# ProPatch_Main.net
KiCad netlist of a schematic drawn in Altium Designer
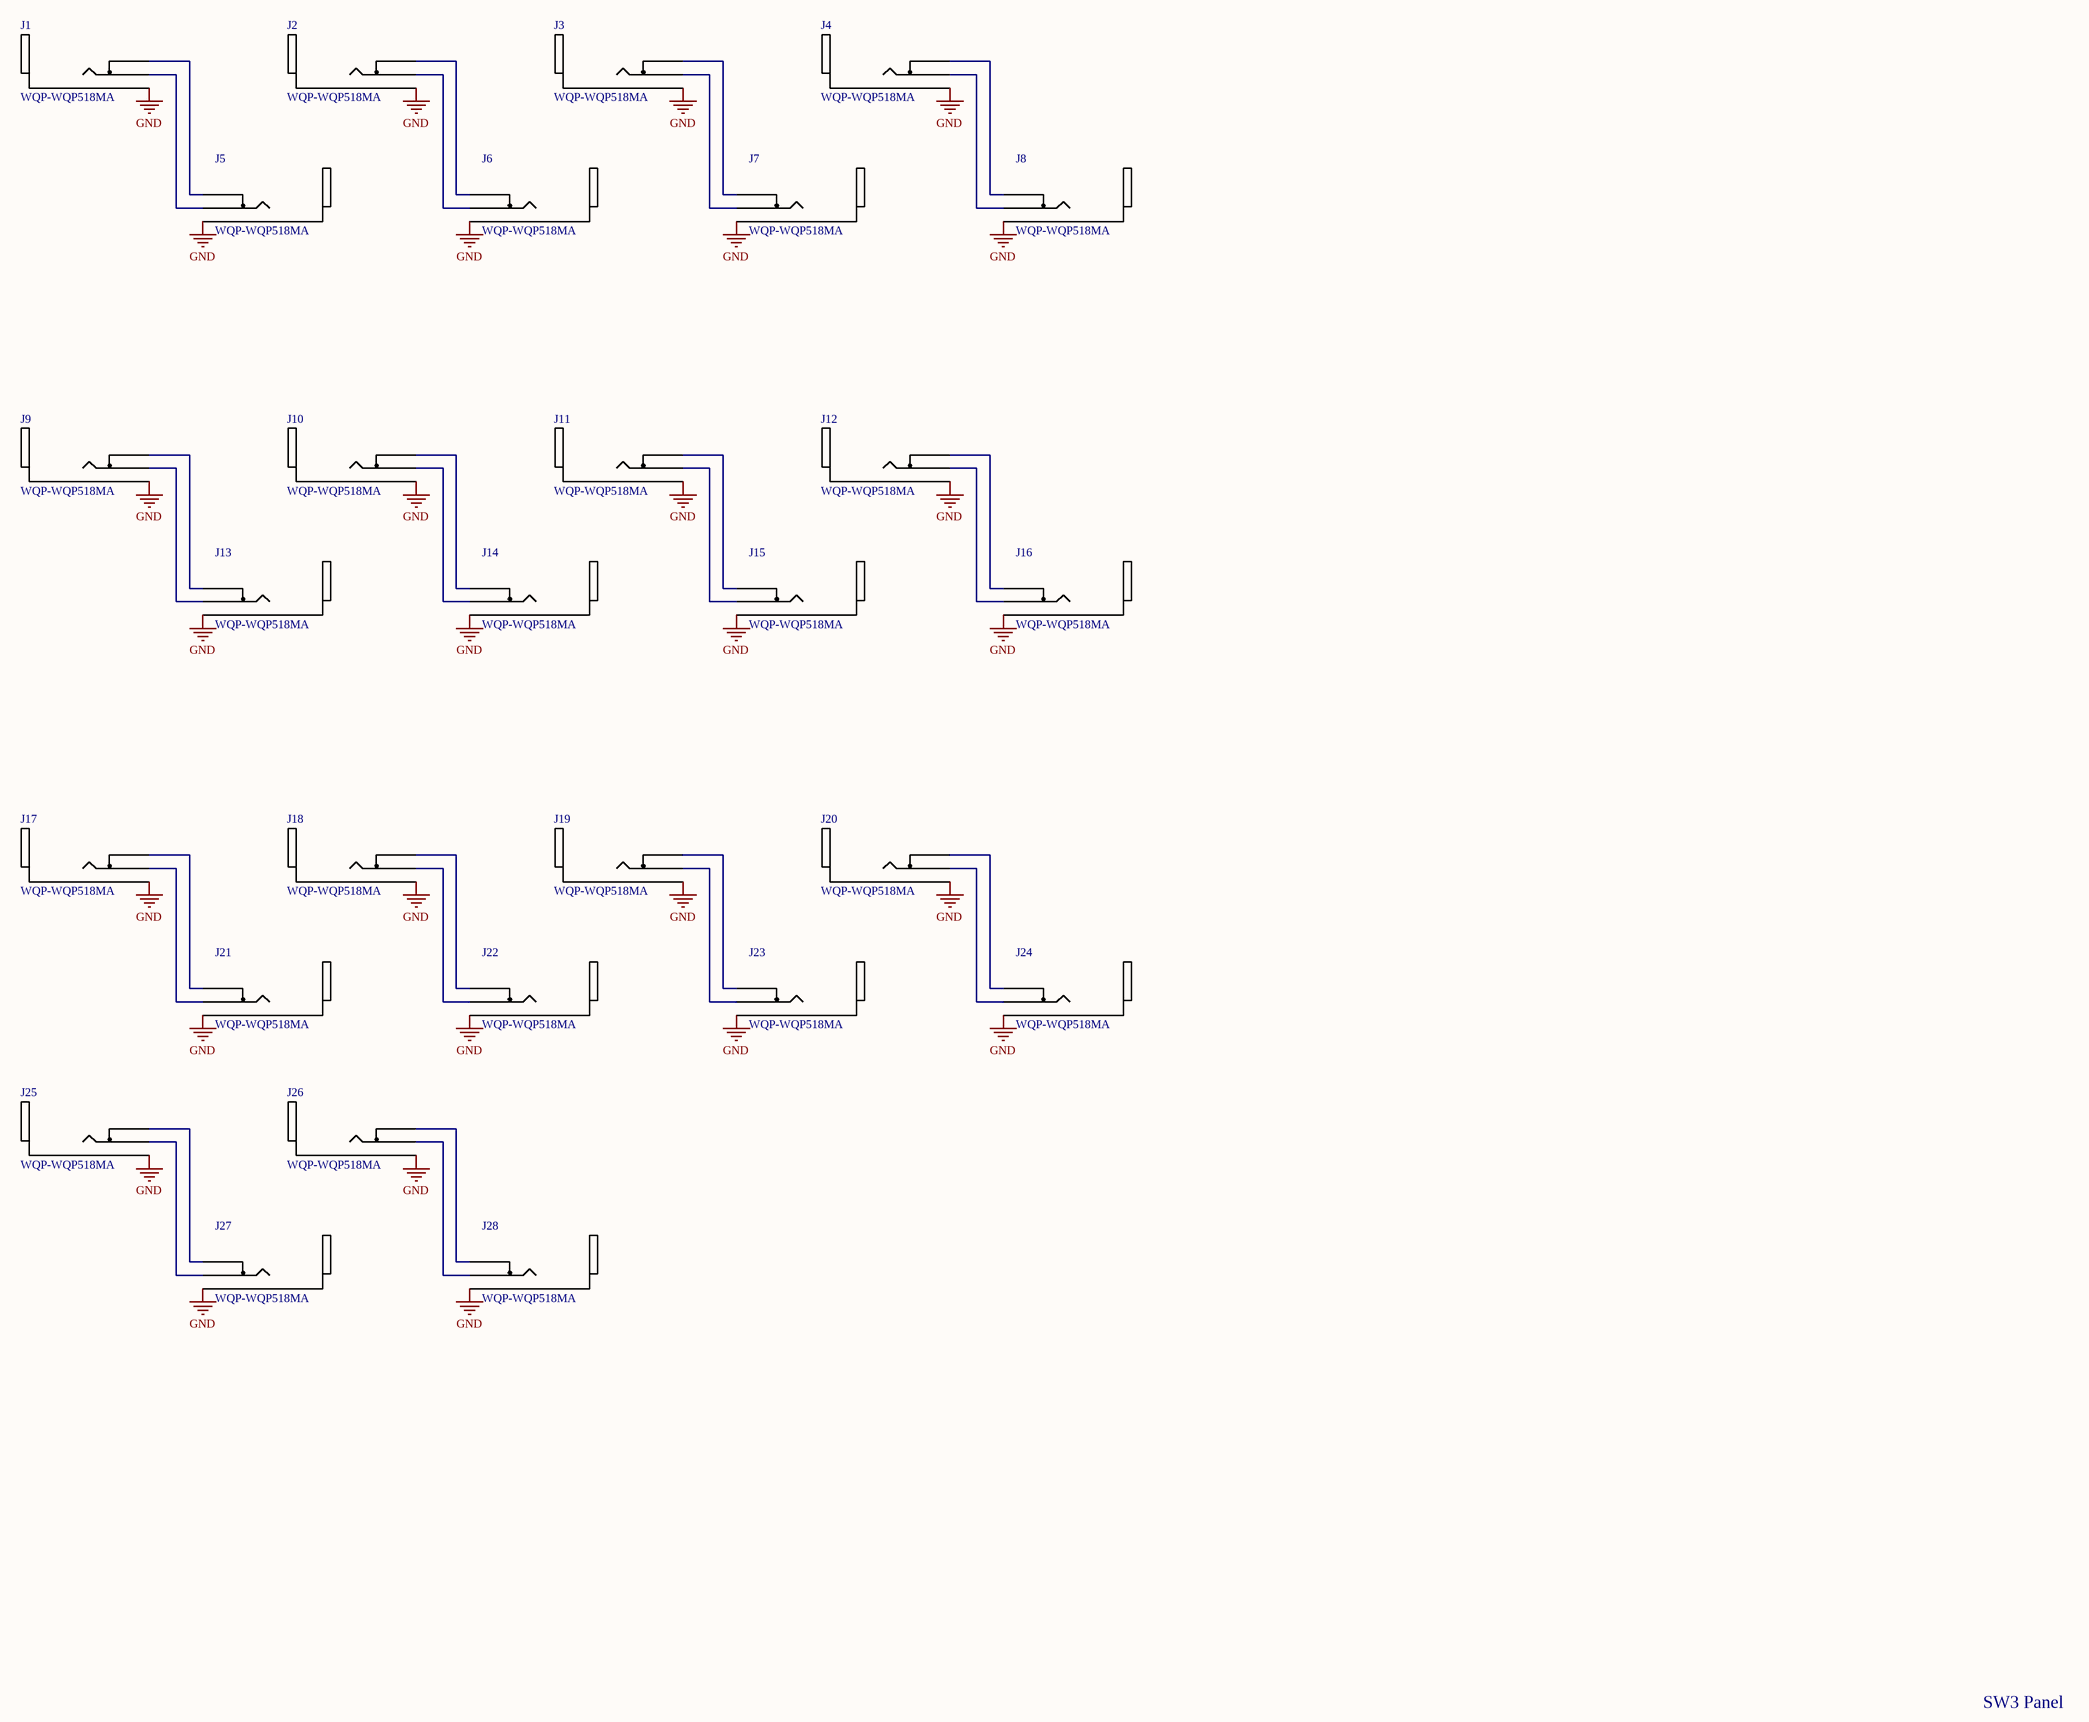
[diagram p0: ProPatch Main.SchDoc]

(export (version "E")
  (design (tool "Eeschema 10.0.6"))
  (components
    (comp (ref "J1")
      (value "WQP-WQP518MA")
      (footprint "PJ301M-12")
      (description "CONN 3.5mm VIRTICAL MONO w/ NORMAL")
      (fields (field (name "MANUFACTURER") "QingPu"))
      (libsource (lib "Connectors") (part "PJ301M-12"))
    )
    (comp (ref "J2")
      (value "WQP-WQP518MA")
      (footprint "PJ301M-12")
      (description "CONN 3.5mm VIRTICAL MONO w/ NORMAL")
      (fields (field (name "MANUFACTURER") "QingPu"))
      (libsource (lib "Connectors") (part "PJ301M-12"))
    )
    (comp (ref "J3")
      (value "WQP-WQP518MA")
      (footprint "PJ301M-12")
      (description "CONN 3.5mm VIRTICAL MONO w/ NORMAL")
      (fields (field (name "MANUFACTURER") "QingPu"))
      (libsource (lib "Connectors") (part "PJ301M-12"))
    )
    (comp (ref "J4")
      (value "WQP-WQP518MA")
      (footprint "PJ301M-12")
      (description "CONN 3.5mm VIRTICAL MONO w/ NORMAL")
      (fields (field (name "MANUFACTURER") "QingPu"))
      (libsource (lib "Connectors") (part "PJ301M-12"))
    )
    (comp (ref "J5")
      (value "WQP-WQP518MA")
      (footprint "PJ301M-12")
      (description "CONN 3.5mm VIRTICAL MONO w/ NORMAL")
      (fields (field (name "MANUFACTURER") "QingPu"))
      (libsource (lib "Connectors") (part "PJ301M-12"))
    )
    (comp (ref "J6")
      (value "WQP-WQP518MA")
      (footprint "PJ301M-12")
      (description "CONN 3.5mm VIRTICAL MONO w/ NORMAL")
      (fields (field (name "MANUFACTURER") "QingPu"))
      (libsource (lib "Connectors") (part "PJ301M-12"))
    )
    (comp (ref "J7")
      (value "WQP-WQP518MA")
      (footprint "PJ301M-12")
      (description "CONN 3.5mm VIRTICAL MONO w/ NORMAL")
      (fields (field (name "MANUFACTURER") "QingPu"))
      (libsource (lib "Connectors") (part "PJ301M-12"))
    )
    (comp (ref "J8")
      (value "WQP-WQP518MA")
      (footprint "PJ301M-12")
      (description "CONN 3.5mm VIRTICAL MONO w/ NORMAL")
      (fields (field (name "MANUFACTURER") "QingPu"))
      (libsource (lib "Connectors") (part "PJ301M-12"))
    )
    (comp (ref "J9")
      (value "WQP-WQP518MA")
      (footprint "PJ301M-12")
      (description "CONN 3.5mm VIRTICAL MONO w/ NORMAL")
      (fields (field (name "MANUFACTURER") "QingPu"))
      (libsource (lib "Connectors") (part "PJ301M-12"))
    )
    (comp (ref "J10")
      (value "WQP-WQP518MA")
      (footprint "PJ301M-12")
      (description "CONN 3.5mm VIRTICAL MONO w/ NORMAL")
      (fields (field (name "MANUFACTURER") "QingPu"))
      (libsource (lib "Connectors") (part "PJ301M-12"))
    )
    (comp (ref "J11")
      (value "WQP-WQP518MA")
      (footprint "PJ301M-12")
      (description "CONN 3.5mm VIRTICAL MONO w/ NORMAL")
      (fields (field (name "MANUFACTURER") "QingPu"))
      (libsource (lib "Connectors") (part "PJ301M-12"))
    )
    (comp (ref "J12")
      (value "WQP-WQP518MA")
      (footprint "PJ301M-12")
      (description "CONN 3.5mm VIRTICAL MONO w/ NORMAL")
      (fields (field (name "MANUFACTURER") "QingPu"))
      (libsource (lib "Connectors") (part "PJ301M-12"))
    )
    (comp (ref "J13")
      (value "WQP-WQP518MA")
      (footprint "PJ301M-12")
      (description "CONN 3.5mm VIRTICAL MONO w/ NORMAL")
      (fields (field (name "MANUFACTURER") "QingPu"))
      (libsource (lib "Connectors") (part "PJ301M-12"))
    )
    (comp (ref "J14")
      (value "WQP-WQP518MA")
      (footprint "PJ301M-12")
      (description "CONN 3.5mm VIRTICAL MONO w/ NORMAL")
      (fields (field (name "MANUFACTURER") "QingPu"))
      (libsource (lib "Connectors") (part "PJ301M-12"))
    )
    (comp (ref "J15")
      (value "WQP-WQP518MA")
      (footprint "PJ301M-12")
      (description "CONN 3.5mm VIRTICAL MONO w/ NORMAL")
      (fields (field (name "MANUFACTURER") "QingPu"))
      (libsource (lib "Connectors") (part "PJ301M-12"))
    )
    (comp (ref "J16")
      (value "WQP-WQP518MA")
      (footprint "PJ301M-12")
      (description "CONN 3.5mm VIRTICAL MONO w/ NORMAL")
      (fields (field (name "MANUFACTURER") "QingPu"))
      (libsource (lib "Connectors") (part "PJ301M-12"))
    )
    (comp (ref "J17")
      (value "WQP-WQP518MA")
      (footprint "PJ301M-12")
      (description "CONN 3.5mm VIRTICAL MONO w/ NORMAL")
      (fields (field (name "MANUFACTURER") "QingPu"))
      (libsource (lib "Connectors") (part "PJ301M-12"))
    )
    (comp (ref "J18")
      (value "WQP-WQP518MA")
      (footprint "PJ301M-12")
      (description "CONN 3.5mm VIRTICAL MONO w/ NORMAL")
      (fields (field (name "MANUFACTURER") "QingPu"))
      (libsource (lib "Connectors") (part "PJ301M-12"))
    )
    (comp (ref "J19")
      (value "WQP-WQP518MA")
      (footprint "PJ301M-12")
      (description "CONN 3.5mm VIRTICAL MONO w/ NORMAL")
      (fields (field (name "MANUFACTURER") "QingPu"))
      (libsource (lib "Connectors") (part "PJ301M-12"))
    )
    (comp (ref "J20")
      (value "WQP-WQP518MA")
      (footprint "PJ301M-12")
      (description "CONN 3.5mm VIRTICAL MONO w/ NORMAL")
      (fields (field (name "MANUFACTURER") "QingPu"))
      (libsource (lib "Connectors") (part "PJ301M-12"))
    )
    (comp (ref "J21")
      (value "WQP-WQP518MA")
      (footprint "PJ301M-12")
      (description "CONN 3.5mm VIRTICAL MONO w/ NORMAL")
      (fields (field (name "MANUFACTURER") "QingPu"))
      (libsource (lib "Connectors") (part "PJ301M-12"))
    )
    (comp (ref "J22")
      (value "WQP-WQP518MA")
      (footprint "PJ301M-12")
      (description "CONN 3.5mm VIRTICAL MONO w/ NORMAL")
      (fields (field (name "MANUFACTURER") "QingPu"))
      (libsource (lib "Connectors") (part "PJ301M-12"))
    )
    (comp (ref "J23")
      (value "WQP-WQP518MA")
      (footprint "PJ301M-12")
      (description "CONN 3.5mm VIRTICAL MONO w/ NORMAL")
      (fields (field (name "MANUFACTURER") "QingPu"))
      (libsource (lib "Connectors") (part "PJ301M-12"))
    )
    (comp (ref "J24")
      (value "WQP-WQP518MA")
      (footprint "PJ301M-12")
      (description "CONN 3.5mm VIRTICAL MONO w/ NORMAL")
      (fields (field (name "MANUFACTURER") "QingPu"))
      (libsource (lib "Connectors") (part "PJ301M-12"))
    )
    (comp (ref "J25")
      (value "WQP-WQP518MA")
      (footprint "PJ301M-12")
      (description "CONN 3.5mm VIRTICAL MONO w/ NORMAL")
      (fields (field (name "MANUFACTURER") "QingPu"))
      (libsource (lib "Connectors") (part "PJ301M-12"))
    )
    (comp (ref "J26")
      (value "WQP-WQP518MA")
      (footprint "PJ301M-12")
      (description "CONN 3.5mm VIRTICAL MONO w/ NORMAL")
      (fields (field (name "MANUFACTURER") "QingPu"))
      (libsource (lib "Connectors") (part "PJ301M-12"))
    )
    (comp (ref "J27")
      (value "WQP-WQP518MA")
      (footprint "PJ301M-12")
      (description "CONN 3.5mm VIRTICAL MONO w/ NORMAL")
      (fields (field (name "MANUFACTURER") "QingPu"))
      (libsource (lib "Connectors") (part "PJ301M-12"))
    )
    (comp (ref "J28")
      (value "WQP-WQP518MA")
      (footprint "PJ301M-12")
      (description "CONN 3.5mm VIRTICAL MONO w/ NORMAL")
      (fields (field (name "MANUFACTURER") "QingPu"))
      (libsource (lib "Connectors") (part "PJ301M-12"))
    )
  )
  (nets
    (net (code "1") (name "GND") (class "Default")
      (node (ref "J1") (pin "1") (pinfunction "1_1") (pintype "passive"))
      (node (ref "J10") (pin "1") (pinfunction "1_1") (pintype "passive"))
      (node (ref "J11") (pin "1") (pinfunction "1_1") (pintype "passive"))
      (node (ref "J12") (pin "1") (pinfunction "1_1") (pintype "passive"))
      (node (ref "J13") (pin "1") (pinfunction "1_1") (pintype "passive"))
      (node (ref "J14") (pin "1") (pinfunction "1_1") (pintype "passive"))
      (node (ref "J15") (pin "1") (pinfunction "1_1") (pintype "passive"))
      (node (ref "J16") (pin "1") (pinfunction "1_1") (pintype "passive"))
      (node (ref "J17") (pin "1") (pinfunction "1_1") (pintype "passive"))
      (node (ref "J18") (pin "1") (pinfunction "1_1") (pintype "passive"))
      (node (ref "J19") (pin "1") (pinfunction "1_1") (pintype "passive"))
      (node (ref "J2") (pin "1") (pinfunction "1_1") (pintype "passive"))
      (node (ref "J20") (pin "1") (pinfunction "1_1") (pintype "passive"))
      (node (ref "J21") (pin "1") (pinfunction "1_1") (pintype "passive"))
      (node (ref "J22") (pin "1") (pinfunction "1_1") (pintype "passive"))
      (node (ref "J23") (pin "1") (pinfunction "1_1") (pintype "passive"))
      (node (ref "J24") (pin "1") (pinfunction "1_1") (pintype "passive"))
      (node (ref "J25") (pin "1") (pinfunction "1_1") (pintype "passive"))
      (node (ref "J26") (pin "1") (pinfunction "1_1") (pintype "passive"))
      (node (ref "J27") (pin "1") (pinfunction "1_1") (pintype "passive"))
      (node (ref "J28") (pin "1") (pinfunction "1_1") (pintype "passive"))
      (node (ref "J3") (pin "1") (pinfunction "1_1") (pintype "passive"))
      (node (ref "J4") (pin "1") (pinfunction "1_1") (pintype "passive"))
      (node (ref "J5") (pin "1") (pinfunction "1_1") (pintype "passive"))
      (node (ref "J6") (pin "1") (pinfunction "1_1") (pintype "passive"))
      (node (ref "J7") (pin "1") (pinfunction "1_1") (pintype "passive"))
      (node (ref "J8") (pin "1") (pinfunction "1_1") (pintype "passive"))
      (node (ref "J9") (pin "1") (pinfunction "1_1") (pintype "passive"))
    )
    (net (code "2") (name "Net-(J1-Pad2)") (class "Default")
      (node (ref "J1") (pin "2") (pinfunction "2_2") (pintype "passive"))
      (node (ref "J5") (pin "2") (pinfunction "2_2") (pintype "passive"))
    )
    (net (code "3") (name "Net-(J1-Pad3)") (class "Default")
      (node (ref "J1") (pin "3") (pinfunction "3_3") (pintype "passive"))
      (node (ref "J5") (pin "3") (pinfunction "3_3") (pintype "passive"))
    )
    (net (code "4") (name "Net-(J2-Pad2)") (class "Default")
      (node (ref "J2") (pin "2") (pinfunction "2_2") (pintype "passive"))
      (node (ref "J6") (pin "2") (pinfunction "2_2") (pintype "passive"))
    )
    (net (code "5") (name "Net-(J2-Pad3)") (class "Default")
      (node (ref "J2") (pin "3") (pinfunction "3_3") (pintype "passive"))
      (node (ref "J6") (pin "3") (pinfunction "3_3") (pintype "passive"))
    )
    (net (code "6") (name "Net-(J3-Pad2)") (class "Default")
      (node (ref "J3") (pin "2") (pinfunction "2_2") (pintype "passive"))
      (node (ref "J7") (pin "2") (pinfunction "2_2") (pintype "passive"))
    )
    (net (code "7") (name "Net-(J3-Pad3)") (class "Default")
      (node (ref "J3") (pin "3") (pinfunction "3_3") (pintype "passive"))
      (node (ref "J7") (pin "3") (pinfunction "3_3") (pintype "passive"))
    )
    (net (code "8") (name "Net-(J4-Pad2)") (class "Default")
      (node (ref "J4") (pin "2") (pinfunction "2_2") (pintype "passive"))
      (node (ref "J8") (pin "2") (pinfunction "2_2") (pintype "passive"))
    )
    (net (code "9") (name "Net-(J4-Pad3)") (class "Default")
      (node (ref "J4") (pin "3") (pinfunction "3_3") (pintype "passive"))
      (node (ref "J8") (pin "3") (pinfunction "3_3") (pintype "passive"))
    )
    (net (code "10") (name "Net-(J10-Pad2)") (class "Default")
      (node (ref "J10") (pin "2") (pinfunction "2_2") (pintype "passive"))
      (node (ref "J14") (pin "2") (pinfunction "2_2") (pintype "passive"))
    )
    (net (code "11") (name "Net-(J10-Pad3)") (class "Default")
      (node (ref "J10") (pin "3") (pinfunction "3_3") (pintype "passive"))
      (node (ref "J14") (pin "3") (pinfunction "3_3") (pintype "passive"))
    )
    (net (code "12") (name "Net-(J11-Pad2)") (class "Default")
      (node (ref "J11") (pin "2") (pinfunction "2_2") (pintype "passive"))
      (node (ref "J15") (pin "2") (pinfunction "2_2") (pintype "passive"))
    )
    (net (code "13") (name "Net-(J11-Pad3)") (class "Default")
      (node (ref "J11") (pin "3") (pinfunction "3_3") (pintype "passive"))
      (node (ref "J15") (pin "3") (pinfunction "3_3") (pintype "passive"))
    )
    (net (code "14") (name "Net-(J12-Pad2)") (class "Default")
      (node (ref "J12") (pin "2") (pinfunction "2_2") (pintype "passive"))
      (node (ref "J16") (pin "2") (pinfunction "2_2") (pintype "passive"))
    )
    (net (code "15") (name "Net-(J12-Pad3)") (class "Default")
      (node (ref "J12") (pin "3") (pinfunction "3_3") (pintype "passive"))
      (node (ref "J16") (pin "3") (pinfunction "3_3") (pintype "passive"))
    )
    (net (code "16") (name "Net-(J13-Pad2)") (class "Default")
      (node (ref "J13") (pin "2") (pinfunction "2_2") (pintype "passive"))
      (node (ref "J9") (pin "2") (pinfunction "2_2") (pintype "passive"))
    )
    (net (code "17") (name "Net-(J13-Pad3)") (class "Default")
      (node (ref "J13") (pin "3") (pinfunction "3_3") (pintype "passive"))
      (node (ref "J9") (pin "3") (pinfunction "3_3") (pintype "passive"))
    )
    (net (code "18") (name "Net-(J17-Pad2)") (class "Default")
      (node (ref "J17") (pin "2") (pinfunction "2_2") (pintype "passive"))
      (node (ref "J21") (pin "2") (pinfunction "2_2") (pintype "passive"))
    )
    (net (code "19") (name "Net-(J17-Pad3)") (class "Default")
      (node (ref "J17") (pin "3") (pinfunction "3_3") (pintype "passive"))
      (node (ref "J21") (pin "3") (pinfunction "3_3") (pintype "passive"))
    )
    (net (code "20") (name "Net-(J18-Pad2)") (class "Default")
      (node (ref "J18") (pin "2") (pinfunction "2_2") (pintype "passive"))
      (node (ref "J22") (pin "2") (pinfunction "2_2") (pintype "passive"))
    )
    (net (code "21") (name "Net-(J18-Pad3)") (class "Default")
      (node (ref "J18") (pin "3") (pinfunction "3_3") (pintype "passive"))
      (node (ref "J22") (pin "3") (pinfunction "3_3") (pintype "passive"))
    )
    (net (code "22") (name "Net-(J19-Pad2)") (class "Default")
      (node (ref "J19") (pin "2") (pinfunction "2_2") (pintype "passive"))
      (node (ref "J23") (pin "2") (pinfunction "2_2") (pintype "passive"))
    )
    (net (code "23") (name "Net-(J19-Pad3)") (class "Default")
      (node (ref "J19") (pin "3") (pinfunction "3_3") (pintype "passive"))
      (node (ref "J23") (pin "3") (pinfunction "3_3") (pintype "passive"))
    )
    (net (code "24") (name "Net-(J20-Pad2)") (class "Default")
      (node (ref "J20") (pin "2") (pinfunction "2_2") (pintype "passive"))
      (node (ref "J24") (pin "2") (pinfunction "2_2") (pintype "passive"))
    )
    (net (code "25") (name "Net-(J20-Pad3)") (class "Default")
      (node (ref "J20") (pin "3") (pinfunction "3_3") (pintype "passive"))
      (node (ref "J24") (pin "3") (pinfunction "3_3") (pintype "passive"))
    )
    (net (code "26") (name "Net-(J25-Pad2)") (class "Default")
      (node (ref "J25") (pin "2") (pinfunction "2_2") (pintype "passive"))
      (node (ref "J27") (pin "2") (pinfunction "2_2") (pintype "passive"))
    )
    (net (code "27") (name "Net-(J25-Pad3)") (class "Default")
      (node (ref "J25") (pin "3") (pinfunction "3_3") (pintype "passive"))
      (node (ref "J27") (pin "3") (pinfunction "3_3") (pintype "passive"))
    )
    (net (code "28") (name "Net-(J26-Pad2)") (class "Default")
      (node (ref "J26") (pin "2") (pinfunction "2_2") (pintype "passive"))
      (node (ref "J28") (pin "2") (pinfunction "2_2") (pintype "passive"))
    )
    (net (code "29") (name "Net-(J26-Pad3)") (class "Default")
      (node (ref "J26") (pin "3") (pinfunction "3_3") (pintype "passive"))
      (node (ref "J28") (pin "3") (pinfunction "3_3") (pintype "passive"))
    )
  )
)
